# SH1_-_POWER.net
KiCad netlist of a schematic drawn in Altium Designer
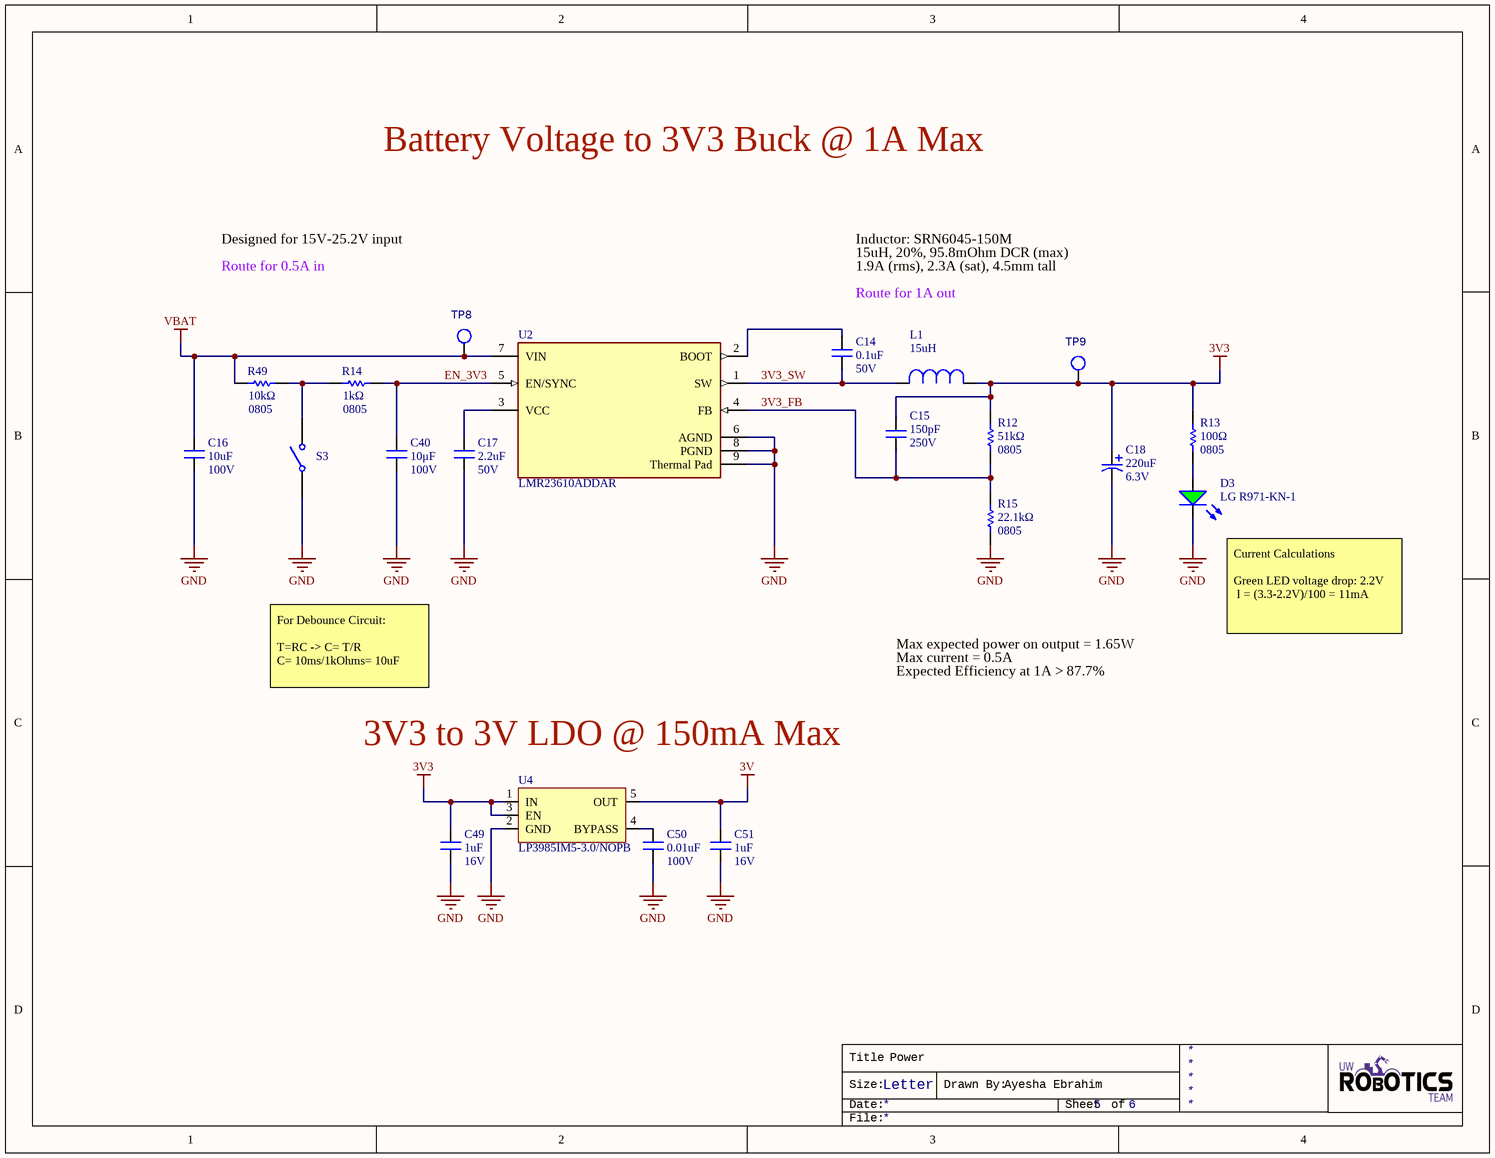
[diagram p0: SH1 - POWER.SchDoc]

(export (version "E")
  (design (tool "Eeschema 10.0.6"))
  (components
    (comp (ref "C14")
      (value "0.1uF")
      (footprint "CAPC2012X140N")
      (description "CAP CER 0.1UF 50V X7R 0805")
      (fields
        (field (name "TOLERANCE") "10%")
        (field (name "VOLTAGE RATING") "50V")
        (field (name "Comment") "CAP_0.1uF_50V_0805")
      )
      (libsource (lib "UWRT_Schematic_Library_2020") (part "CAP_0.1uF_50V_0805"))
    )
    (comp (ref "C15")
      (value "150pF")
      (footprint "CAPC2012X140N")
      (description "CAP CER 150PF 250V C0G/NP0 0805")
      (fields
        (field (name "TOLERANCE") "5%")
        (field (name "VOLTAGE RATING") "250V")
        (field (name "Comment") "CAP_150pF_250V_0805")
      )
      (libsource (lib "UWRT_Schematic_Library_2020") (part "CAP_150pF_250V_0805"))
    )
    (comp (ref "C16")
      (value "10uF")
      (footprint "CAPC1210(3225)")
      (description "CAP CER 10UF 100V X7S 1210")
      (fields (field (name "VOLTAGE RATING") "100V") (field (name "Comment") "CAP_10uF_100V_1210"))
      (libsource (lib "UWRT_Schematic_Library_2020") (part "CAP_10uF_100V_1210"))
    )
    (comp (ref "C17")
      (value "2.2uF")
      (footprint "CAPC1206(3216)")
      (description "CAP CER 2.2UF 50V X7R 1206")
      (fields
        (field (name "TOLERANCE") "10%")
        (field (name "VOLTAGE") "50V")
        (field (name "VOLTAGE RATING") "50V")
      )
      (libsource (lib "UWRT_Schematic_Library_2020") (part "CAP_2.2uF_50V_1206"))
    )
    (comp (ref "C18")
      (value "220uF")
      (footprint "PCAP_SVP_B6_PA00")
      (description "CAP ALUM POLY 220UF 20% 6.3V SMD")
      (fields (field (name "VOLTAGE RATING") "6.3V") (field (name "Comment") "CAP_220uF_6.3V_SMD"))
      (libsource (lib "UWRT_Schematic_Library_2020") (part "CAP_220uF_6.3V_SMD"))
    )
    (comp (ref "C40")
      (value "10μF")
      (footprint "CAPC1210(3225)")
      (description "CAP CER 10uF 100V X7S 10% 1210")
      (fields
        (field (name "TOLERANCE") "10%")
        (field (name "VOLTAGE RATING") "100V")
        (field (name "Comment") "CAP_10uF_100V_1210")
      )
      (libsource (lib "") (part "CAP_10uF_100V_1210_1"))
    )
    (comp (ref "C49")
      (value "1uF")
      (footprint "CAPC2012X140N")
      (description "CAP CER 1UF 16V X7R 0805")
      (fields
        (field (name "TOLERANCE") "10%")
        (field (name "VOLTAGE RATING") "16V")
        (field (name "Comment") "CAP_1uF_16V_0805")
      )
      (libsource (lib "UWRT_Schematic_Library_2020") (part "CAP_1uF_16V_0805"))
    )
    (comp (ref "C50")
      (value "0.01uF")
      (footprint "CAPC2012X140N")
      (description "CAP CER 10000PF 100V X7R 0805")
      (fields
        (field (name "TOLERANCE") "10%")
        (field (name "VOLTAGE RATING") "100V")
        (field (name "Comment") "CAP_0.01uF_100V_0805")
      )
      (libsource (lib "UWRT_Schematic_Library_2020") (part "CAP_0.01uF_100V_0805"))
    )
    (comp (ref "C51")
      (value "1uF")
      (footprint "CAPC2012X140N")
      (description "CAP CER 1UF 16V X7R 0805")
      (fields
        (field (name "TOLERANCE") "10%")
        (field (name "VOLTAGE RATING") "16V")
        (field (name "Comment") "CAP_1uF_16V_0805")
      )
      (libsource (lib "UWRT_Schematic_Library_2020") (part "CAP_1uF_16V_0805"))
    )
    (comp (ref "D3")
      (value "DIO_LED_G")
      (footprint "LED_0805_LINE")
      (description "LED GREEN DIFFUSED 0805 SMD")
      (fields (field (name "MANUFACTURER PART NUMBER 1") "LG R971-KN-1"))
      (libsource (lib "UWRT_Schematic_Library_2020") (part "DIO_LED_G"))
    )
    (comp (ref "L1")
      (value "SRN6045-150M")
      (footprint "IND_BOURNS_SRN6045")
      (description "FIXED IND 15UH 1.9A 95.8MOHM SMD")
      (fields (field (name "TOLERANCE") "20%") (field (name "INDUCTANCE") "15uH"))
      (libsource (lib "UWRT_Schematic_Library_2020") (part "IND_15uH_1.9A"))
    )
    (comp (ref "R12")
      (value "51kΩ")
      (footprint "RESC2012X60N")
      (description "RES SMD 51K OHM 1% 1/8W 0805")
      (fields
        (field (name "CASE CODE (IMPERIAL)") "0805")
        (field (name "TOLERANCE") "1%")
        (field (name "Comment") "RES_51kΩ_0805")
      )
      (libsource (lib "UWRT_Schematic_Library_2020") (part "RES_51kΩ_0805"))
    )
    (comp (ref "R13")
      (value "100Ω")
      (footprint "RESC2012X60N")
      (description "RES SMD 100 OHM 1% 1/8W 0805")
      (fields (field (name "CASE CODE (IMPERIAL)") "0805") (field (name "Comment") "RES_100Ω_0805"))
      (libsource (lib "UWRT_Schematic_Library_2020") (part "RES_100Ω_0805"))
    )
    (comp (ref "R14")
      (value "1kΩ")
      (footprint "RESC2012X60N")
      (description "RES SMD 1K OHM 1% 1/8W 0805")
      (fields (field (name "TOLERANCE") "1%") (field (name "CASE CODE (IMPERIAL)") "0805"))
      (libsource (lib "UWRT_Schematic_Library_2020") (part "RES_1kΩ_0805"))
    )
    (comp (ref "R15")
      (value "RES_22.1kΩ_0805")
      (footprint "RESC2012X60N")
      (description "RES SMD 22.1K OHM 1% 1/8W 0805")
      (fields
        (field (name "CASE CODE (IMPERIAL)") "0805")
        (field (name "RESISTANCE") "22.1kΩ")
        (field (name "TOLERANCE") "1%")
      )
      (libsource (lib "UWRT_Schematic_Library_2020") (part "RES_22.1kΩ_0805"))
    )
    (comp (ref "R49")
      (value "10kΩ")
      (footprint "RESC2012X60N")
      (description "RES SMD 10K OHM 1% 1/8W 0805")
      (fields
        (field (name "TOLERANCE") "1%")
        (field (name "CASE CODE (IMPERIAL)") "0805")
        (field (name "Comment") "RES_10kΩ_0805")
      )
      (libsource (lib "UWRT_Schematic_Library_2020") (part "RES_10kΩ_0805"))
    )
    (comp (ref "S3")
      (value "GF-123-0054")
      (footprint "GF1230054")
      (description "SWITCH SLIDE SPST 500mA (DC) 8.5A (AC) 125V")
      (libsource (lib "UWRT_Schematic_Library_2020") (part "GF-123-0054"))
    )
    (comp (ref "TP8")
      (value "TESTPOINT_LOOP")
      (footprint "TESTPOINT_LOOP")
      (description "Loop testpoint through-hole pad")
      (libsource (lib "UWRT_Schematic_Library_2020") (part "TESTPOINT_LOOP"))
    )
    (comp (ref "TP9")
      (value "TESTPOINT_LOOP")
      (footprint "TESTPOINT_LOOP")
      (description "Loop testpoint through-hole pad")
      (libsource (lib "UWRT_Schematic_Library_2020") (part "TESTPOINT_LOOP"))
    )
    (comp (ref "U2")
      (value "LMR23610ADDAR")
      (footprint "8-SO PowerPad")
      (description "IC REG BUCK ADJUSTABLE 1A 8SOPWR")
      (fields (field (name "OCTOPART") "https://octopart.com/lmr23610addar-texas+instruments-68058948"))
      (libsource (lib "UWRT_Schematic_Library_2020") (part "BUCK_1-28VOUT_1A"))
    )
    (comp (ref "U4")
      (value "LP3985IM5-3.0/NOPB")
      (footprint "SOT23-5")
      (description "IC REG LINEAR 3V 150MA SOT23-5")
      (libsource (lib "UWRT_Schematic_Library_2020") (part "LP3985IM5-3.0/NOPB"))
    )
  )
  (nets
    (net (code "1") (name "/3V3_FB") (class "Default")
      (node (ref "C15") (pin "2") (pinfunction "2_2") (pintype "passive"))
      (node (ref "R12") (pin "1") (pinfunction "1_1") (pintype "passive"))
      (node (ref "R15") (pin "2") (pinfunction "2_2") (pintype "passive"))
      (node (ref "U2") (pin "4") (pinfunction "FB_4") (pintype "input"))
    )
    (net (code "2") (name "/3V3_SW") (class "Default")
      (node (ref "C14") (pin "1") (pinfunction "1_1") (pintype "passive"))
      (node (ref "L1") (pin "2") (pinfunction "2_2") (pintype "passive"))
      (node (ref "U2") (pin "1") (pinfunction "SW_1") (pintype "output"))
    )
    (net (code "3") (name "/EN_3V3") (class "Default")
      (node (ref "C40") (pin "2") (pinfunction "2_2") (pintype "passive"))
      (node (ref "R14") (pin "2") (pinfunction "2_2") (pintype "passive"))
      (node (ref "U2") (pin "5") (pinfunction "EN/SYNC_5") (pintype "input"))
    )
    (net (code "4") (name "3V") (class "Default")
      (node (ref "C51") (pin "2") (pinfunction "2_2") (pintype "passive"))
      (node (ref "U4") (pin "5") (pinfunction "OUT_5") (pintype "passive"))
    )
    (net (code "5") (name "3V3") (class "Default")
      (node (ref "C15") (pin "1") (pinfunction "1_1") (pintype "passive"))
      (node (ref "C18") (pin "1") (pinfunction "1_1") (pintype "passive"))
      (node (ref "C49") (pin "2") (pinfunction "2_2") (pintype "passive"))
      (node (ref "L1") (pin "1") (pinfunction "1_1") (pintype "passive"))
      (node (ref "R12") (pin "2") (pinfunction "2_2") (pintype "passive"))
      (node (ref "R13") (pin "2") (pinfunction "2_2") (pintype "passive"))
      (node (ref "TP9") (pin "1") (pintype "passive"))
      (node (ref "U4") (pin "1") (pinfunction "IN_1") (pintype "passive"))
      (node (ref "U4") (pin "3") (pinfunction "EN_3") (pintype "passive"))
    )
    (net (code "6") (name "GND") (class "Default")
      (node (ref "C16") (pin "1") (pinfunction "1_1") (pintype "passive"))
      (node (ref "C17") (pin "1") (pinfunction "1_1") (pintype "passive"))
      (node (ref "C18") (pin "2") (pinfunction "2_2") (pintype "passive"))
      (node (ref "C40") (pin "1") (pinfunction "1_1") (pintype "passive"))
      (node (ref "C49") (pin "1") (pinfunction "1_1") (pintype "passive"))
      (node (ref "C50") (pin "1") (pinfunction "1_1") (pintype "passive"))
      (node (ref "C51") (pin "1") (pinfunction "1_1") (pintype "passive"))
      (node (ref "D3") (pin "2") (pinfunction "K_2") (pintype "passive"))
      (node (ref "R15") (pin "1") (pinfunction "1_1") (pintype "passive"))
      (node (ref "S3") (pin "1") (pintype "passive"))
      (node (ref "U2") (pin "6") (pinfunction "AGND_6") (pintype "power_in"))
      (node (ref "U2") (pin "8") (pinfunction "PGND_8") (pintype "power_in"))
      (node (ref "U2") (pin "9") (pinfunction "Thermal_Pad_9") (pintype "power_in"))
      (node (ref "U4") (pin "2") (pinfunction "GND_2") (pintype "passive"))
    )
    (net (code "7") (name "Net-(D3-A)") (class "Default")
      (node (ref "D3") (pin "1") (pinfunction "A_1") (pintype "passive"))
      (node (ref "R13") (pin "1") (pinfunction "1_1") (pintype "passive"))
    )
    (net (code "8") (name "Net-(R14-Pad1)") (class "Default")
      (node (ref "R14") (pin "1") (pinfunction "1_1") (pintype "passive"))
      (node (ref "R49") (pin "2") (pinfunction "2_2") (pintype "passive"))
      (node (ref "S3") (pin "2") (pintype "passive"))
    )
    (net (code "9") (name "Net-(U2-BOOT)") (class "Default")
      (node (ref "C14") (pin "2") (pinfunction "2_2") (pintype "passive"))
      (node (ref "U2") (pin "2") (pinfunction "BOOT_2") (pintype "output"))
    )
    (net (code "10") (name "Net-(U2-VCC)") (class "Default")
      (node (ref "C17") (pin "2") (pinfunction "2_2") (pintype "passive"))
      (node (ref "U2") (pin "3") (pinfunction "VCC_3") (pintype "power_in"))
    )
    (net (code "11") (name "Net-(U4-BYPASS)") (class "Default")
      (node (ref "C50") (pin "2") (pinfunction "2_2") (pintype "passive"))
      (node (ref "U4") (pin "4") (pinfunction "BYPASS_4") (pintype "passive"))
    )
    (net (code "12") (name "VBAT") (class "Default")
      (node (ref "C16") (pin "2") (pinfunction "2_2") (pintype "passive"))
      (node (ref "R49") (pin "1") (pinfunction "1_1") (pintype "passive"))
      (node (ref "TP8") (pin "1") (pintype "passive"))
      (node (ref "U2") (pin "7") (pinfunction "VIN_7") (pintype "power_in"))
    )
  )
)
